# Pressure_sensor_-_SCP1000-D01.net
KiCad netlist of a schematic drawn in Altium Designer
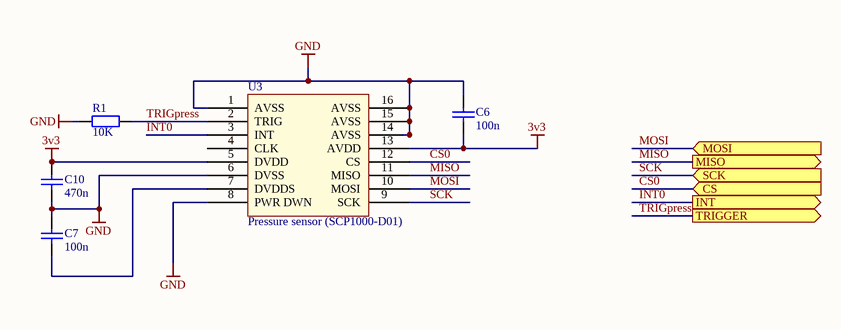
[diagram p0: Pressure sensor - SCP1000-D01.SchDoc]

(export (version "E")
  (design (tool "Eeschema 10.0.6"))
  (components
    (comp (ref "C6")
      (value "100n")
      (footprint "C0805")
      (fields (field (name "TOLERANCE") "0.1") (field (name "AUTHOR") "Willy Pietersz"))
      (libsource (lib "OurDb") (part "cap_NonPolar"))
    )
    (comp (ref "C7")
      (value "100n")
      (footprint "C0805")
      (fields (field (name "TOLERANCE") "0.1") (field (name "AUTHOR") "Willy Pietersz"))
      (libsource (lib "OurDb") (part "cap_NonPolar"))
    )
    (comp (ref "C10")
      (value "470n")
      (footprint "C0805")
      (fields (field (name "TOLERANCE") "0.1") (field (name "AUTHOR") "Willy Pietersz"))
      (libsource (lib "OurDb") (part "cap_NonPolar"))
    )
    (comp (ref "R1")
      (value "10K")
      (footprint "R0805")
      (description "Resistor")
      (fields
        (field (name "POWER") "0.25W")
        (field (name "TOLERANCE") "0.05")
        (field (name "PUBLISHER") "Altium Limited")
        (field (name "AUTHOR") "Willy Pietersz")
      )
      (libsource (lib "OurDb") (part "RESISTOR"))
    )
    (comp (ref "U3")
      (value "Pressure sensor (SCP1000-D01)")
      (footprint "SCP1000-D01")
      (fields (field (name "PART NUMBER") "SCP1000-D01"))
      (libsource (lib "OurDb") (part "SCP1000-D01"))
    )
  )
  (nets
    (net (code "1") (name "/CS0") (class "Default")
      (node (ref "U3") (pin "12") (pinfunction "CS_12") (pintype "passive"))
    )
    (net (code "2") (name "/INT0") (class "Default")
      (node (ref "U3") (pin "3") (pinfunction "INT_3") (pintype "passive"))
    )
    (net (code "3") (name "/MISO") (class "Default")
      (node (ref "U3") (pin "11") (pinfunction "MISO_11") (pintype "passive"))
    )
    (net (code "4") (name "/MOSI") (class "Default")
      (node (ref "U3") (pin "10") (pinfunction "MOSI_10") (pintype "passive"))
    )
    (net (code "5") (name "/SCK") (class "Default")
      (node (ref "U3") (pin "9") (pinfunction "SCK_9") (pintype "passive"))
    )
    (net (code "6") (name "/TRIGpress") (class "Default")
      (node (ref "R1") (pin "2") (pinfunction "2_2") (pintype "passive"))
      (node (ref "U3") (pin "2") (pinfunction "TRIG_2") (pintype "passive"))
    )
    (net (code "7") (name "3v3") (class "Default")
      (node (ref "C10") (pin "2") (pinfunction "2_2") (pintype "passive"))
      (node (ref "C6") (pin "1") (pinfunction "1_1") (pintype "passive"))
      (node (ref "U3") (pin "13") (pinfunction "AVDD_13") (pintype "passive"))
      (node (ref "U3") (pin "5") (pinfunction "DVDD_5") (pintype "passive"))
    )
    (net (code "8") (name "GND") (class "Default")
      (node (ref "C10") (pin "1") (pinfunction "1_1") (pintype "passive"))
      (node (ref "C6") (pin "2") (pinfunction "2_2") (pintype "passive"))
      (node (ref "C7") (pin "2") (pinfunction "2_2") (pintype "passive"))
      (node (ref "R1") (pin "1") (pinfunction "1_1") (pintype "passive"))
      (node (ref "U3") (pin "1") (pinfunction "AVSS_1") (pintype "passive"))
      (node (ref "U3") (pin "14") (pinfunction "AVSS_14") (pintype "passive"))
      (node (ref "U3") (pin "15") (pinfunction "AVSS_15") (pintype "passive"))
      (node (ref "U3") (pin "16") (pinfunction "AVSS_16") (pintype "passive"))
      (node (ref "U3") (pin "6") (pinfunction "DVSS_6") (pintype "passive"))
      (node (ref "U3") (pin "8") (pinfunction "PWR_DWN_8") (pintype "passive"))
    )
    (net (code "9") (name "Net-(U3-DVDDS)") (class "Default")
      (node (ref "C7") (pin "1") (pinfunction "1_1") (pintype "passive"))
      (node (ref "U3") (pin "7") (pinfunction "DVDDS_7") (pintype "passive"))
    )
    (net (code "10") (name "unconnected-(U3-CLK-Pad4)") (class "Default")
      (node (ref "U3") (pin "4") (pinfunction "CLK_4") (pintype "passive"))
    )
  )
)
